# common_board_smd.net
KiCad netlist of a schematic drawn in EAGLE
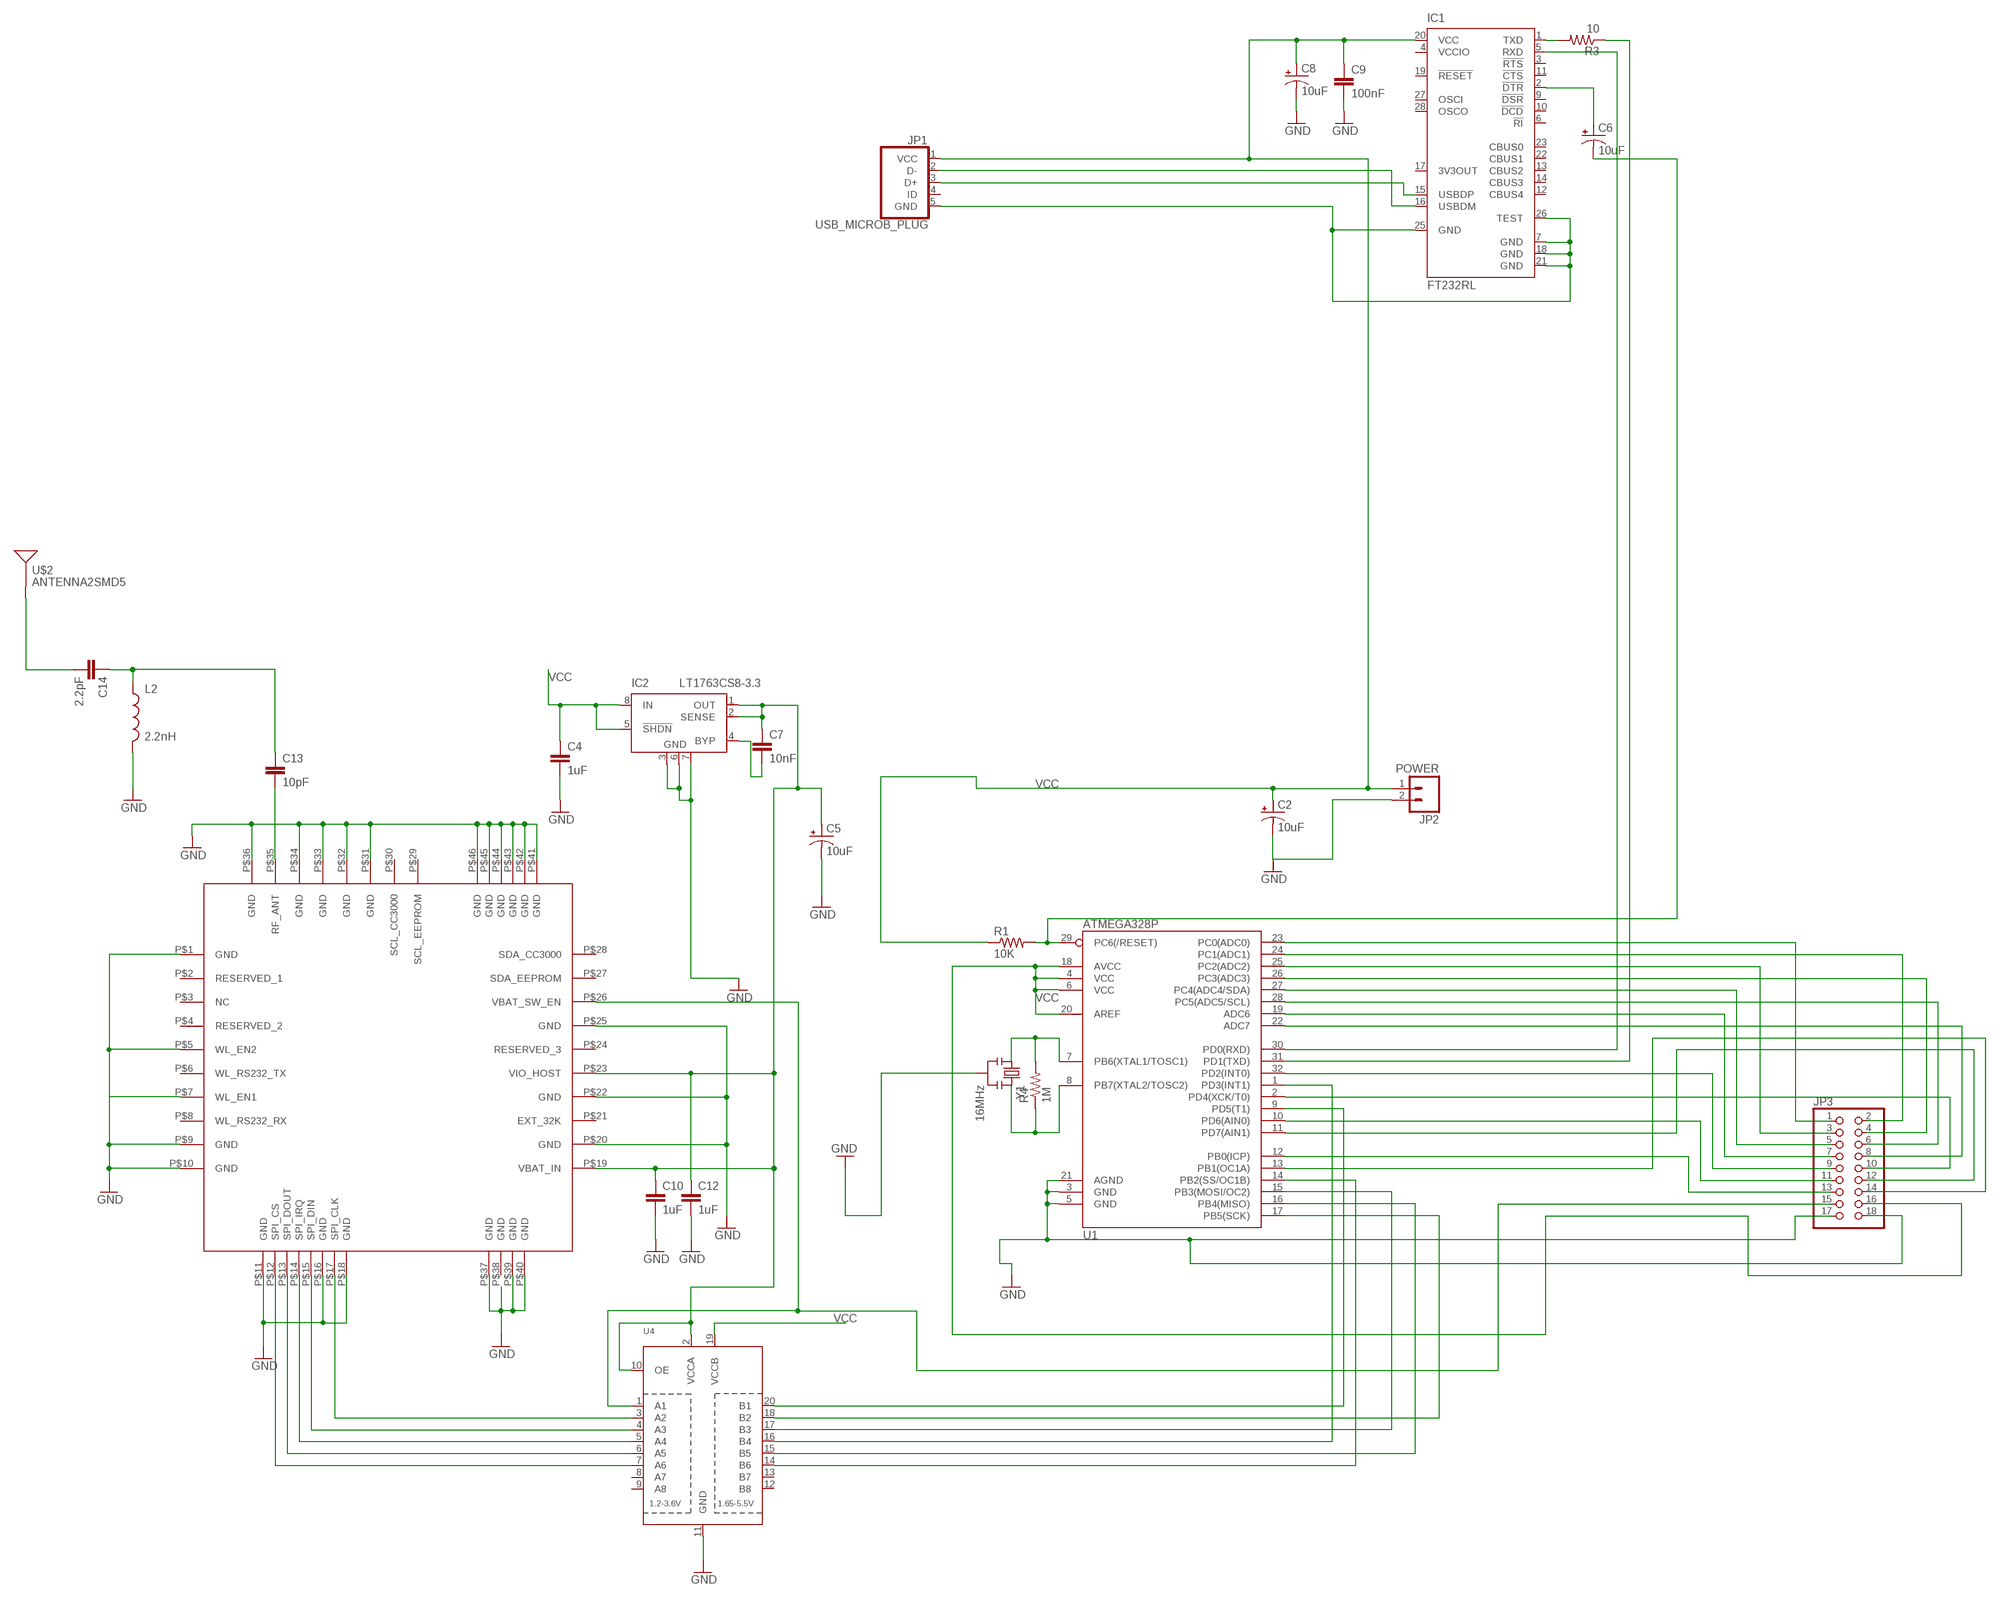
[diagram p0: schematic, sheet 1]

(export (version "E")
  (design (tool "Eeschema 10.0.6"))
  (components
    (comp (ref "C2")
      (value "10uF")
      (footprint "eagle-import:EIA3216")
      (libsource (lib "eagle-import") (part "CAP_POL1206"))
    )
    (comp (ref "C4")
      (value "1uF")
      (footprint "eagle-import:0805")
      (libsource (lib "eagle-import") (part "CAP0805"))
    )
    (comp (ref "C5")
      (value "10uF")
      (footprint "eagle-import:EIA3528")
      (libsource (lib "eagle-import") (part "CAP_POL3528"))
    )
    (comp (ref "C6")
      (value "10uF")
      (footprint "eagle-import:EIA3216")
      (libsource (lib "eagle-import") (part "CAP_POL1206"))
    )
    (comp (ref "C7")
      (value "10nF")
      (footprint "eagle-import:0805")
      (libsource (lib "eagle-import") (part "CAP0805"))
    )
    (comp (ref "C8")
      (value "10uF")
      (footprint "eagle-import:EIA3216")
      (libsource (lib "eagle-import") (part "CAP_POL1206"))
    )
    (comp (ref "C9")
      (value "100nF")
      (footprint "eagle-import:0805")
      (libsource (lib "eagle-import") (part "CAP0805"))
    )
    (comp (ref "C10")
      (value "1uF")
      (footprint "eagle-import:1206")
      (libsource (lib "eagle-import") (part "CAP1206"))
    )
    (comp (ref "C12")
      (value "1uF")
      (footprint "eagle-import:1206")
      (libsource (lib "eagle-import") (part "CAP1206"))
    )
    (comp (ref "C13")
      (value "10pF")
      (footprint "eagle-import:0805")
      (libsource (lib "eagle-import") (part "CAP0805"))
    )
    (comp (ref "C14")
      (value "2.2pF")
      (footprint "eagle-import:0805")
      (libsource (lib "eagle-import") (part "CAP0805"))
    )
    (comp (ref "IC1")
      (value "FT232RL")
      (footprint "eagle-import:SSOP28")
      (libsource (lib "eagle-import") (part "FT232RL"))
    )
    (comp (ref "IC2")
      (value "LT1763CS8-3.3")
      (footprint "eagle-import:SOIC8")
      (libsource (lib "eagle-import") (part "LT1763CS8-3.3"))
    )
    (comp (ref "JP1")
      (value "USB_MICROB_PLUG")
      (footprint "eagle-import:MICRO-B-RA-SMT")
      (libsource (lib "eagle-import") (part "USB_MICROB_PLUG"))
    )
    (comp (ref "JP2")
      (value "POWER")
      (footprint "eagle-import:1X02")
      (libsource (lib "eagle-import") (part "M02PTH"))
    )
    (comp (ref "JP3")
      (value "PINHD-2X9-BIG")
      (footprint "eagle-import:2X09-BIG")
      (libsource (lib "eagle-import") (part "PINHD-2X9-BIG"))
    )
    (comp (ref "L2")
      (value "2.2nH")
      (footprint "eagle-import:0805")
      (libsource (lib "eagle-import") (part "INDUCTOR0805"))
    )
    (comp (ref "R1")
      (value "10K")
      (footprint "eagle-import:0805")
      (libsource (lib "eagle-import") (part "RESISTOR0805-RES"))
    )
    (comp (ref "R3")
      (value "10")
      (footprint "eagle-import:0805")
      (libsource (lib "eagle-import") (part "RESISTOR0805-RES"))
    )
    (comp (ref "R4")
      (value "1M")
      (footprint "eagle-import:0603-RES")
      (libsource (lib "eagle-import") (part "SparkFun-Resistors_RESISTOR0603-RES"))
    )
    (comp (ref "U$1")
      (value "CC3000")
      (footprint "eagle-import:CC3000")
      (fields (field (name "AUTHOR") "Matt Bigarani"))
      (libsource (lib "eagle-import") (part "CC3000"))
    )
    (comp (ref "U$2")
      (value "ANTENNA2SMD5")
      (footprint "eagle-import:ANTENNA-CHIP5")
      (libsource (lib "eagle-import") (part "ANTENNA2SMD5"))
    )
    (comp (ref "U1")
      (value "ATMEGA328P")
      (footprint "eagle-import:TQFP32-08")
      (libsource (lib "eagle-import") (part "ATMEGA328_SMT"))
    )
    (comp (ref "U4")
      (value "TXB0108PWR")
      (footprint "eagle-import:TSSOP20")
      (libsource (lib "eagle-import") (part "TXB0108PWR"))
    )
    (comp (ref "Y1")
      (value "16MHz")
      (footprint "eagle-import:RESONATOR-SMD")
      (libsource (lib "eagle-import") (part "RESONATOR16MHZ"))
    )
  )
  (nets
    (net (code "1") (name "/SCL_CC3000") (class "Default")
      (node (ref "U$1") (pin "P$30") (pinfunction "SCL_CC3000_P$30") (pintype "power_in"))
    )
    (net (code "2") (name "/SCL_EEPROM") (class "Default")
      (node (ref "U$1") (pin "P$29") (pinfunction "SCL_EEPROM_P$29") (pintype "power_in"))
    )
    (net (code "3") (name "/VCC") (class "Default")
      (node (ref "C2") (pin "A") (pinfunction "+_A") (pintype "passive"))
      (node (ref "C4") (pin "1") (pinfunction "1_1") (pintype "passive"))
      (node (ref "C8") (pin "A") (pinfunction "+_A") (pintype "passive"))
      (node (ref "C9") (pin "1") (pinfunction "1_1") (pintype "passive"))
      (node (ref "IC1") (pin "20") (pinfunction "VCC_20") (pintype "power_in"))
      (node (ref "IC2") (pin "5") (pinfunction "~{SHDN}_5") (pintype "input"))
      (node (ref "IC2") (pin "8") (pinfunction "IN_8") (pintype "input"))
      (node (ref "JP1") (pin "1") (pinfunction "VCC_1") (pintype "bidirectional"))
      (node (ref "JP2") (pin "1") (pinfunction "1_1") (pintype "passive"))
      (node (ref "JP3") (pin "16") (pinfunction "16_16") (pintype "passive"))
      (node (ref "R1") (pin "1") (pinfunction "1_1") (pintype "passive"))
      (node (ref "U1") (pin "18") (pinfunction "AVCC_18") (pintype "bidirectional"))
      (node (ref "U1") (pin "20") (pinfunction "AREF_20") (pintype "bidirectional"))
      (node (ref "U1") (pin "4") (pinfunction "VCC_4") (pintype "bidirectional"))
      (node (ref "U1") (pin "6") (pinfunction "VCC_6") (pintype "bidirectional"))
      (node (ref "U4") (pin "19") (pinfunction "VCCB_19") (pintype "bidirectional"))
    )
    (net (code "4") (name "/VCCIO") (class "Default")
      (node (ref "IC1") (pin "4") (pinfunction "VCCIO_4") (pintype "power_in"))
    )
    (net (code "5") (name "GND") (class "Default")
      (node (ref "C10") (pin "2") (pinfunction "2_2") (pintype "passive"))
      (node (ref "C12") (pin "2") (pinfunction "2_2") (pintype "passive"))
      (node (ref "C2") (pin "C") (pinfunction "-_C") (pintype "passive"))
      (node (ref "C4") (pin "2") (pinfunction "2_2") (pintype "passive"))
      (node (ref "C5") (pin "C") (pinfunction "-_C") (pintype "passive"))
      (node (ref "C8") (pin "C") (pinfunction "-_C") (pintype "passive"))
      (node (ref "C9") (pin "2") (pinfunction "2_2") (pintype "passive"))
      (node (ref "IC2") (pin "3") (pinfunction "GND_3") (pintype "power_in"))
      (node (ref "IC2") (pin "6") (pinfunction "GND_6") (pintype "power_in"))
      (node (ref "IC2") (pin "7") (pinfunction "GND_7") (pintype "power_in"))
      (node (ref "JP2") (pin "2") (pinfunction "2_2") (pintype "passive"))
      (node (ref "JP3") (pin "17") (pinfunction "17_17") (pintype "passive"))
      (node (ref "JP3") (pin "18") (pinfunction "18_18") (pintype "passive"))
      (node (ref "L2") (pin "2") (pinfunction "2_2") (pintype "passive"))
      (node (ref "U$1") (pin "P$1") (pinfunction "GND_P$1") (pintype "power_in"))
      (node (ref "U$1") (pin "P$10") (pinfunction "GND_P$10") (pintype "power_in"))
      (node (ref "U$1") (pin "P$11") (pinfunction "GND_P$11") (pintype "power_in"))
      (node (ref "U$1") (pin "P$16") (pinfunction "GND_P$16") (pintype "power_in"))
      (node (ref "U$1") (pin "P$18") (pinfunction "GND_P$18") (pintype "power_in"))
      (node (ref "U$1") (pin "P$20") (pinfunction "GND_P$20") (pintype "bidirectional"))
      (node (ref "U$1") (pin "P$22") (pinfunction "GND_P$22") (pintype "bidirectional"))
      (node (ref "U$1") (pin "P$25") (pinfunction "GND_P$25") (pintype "bidirectional"))
      (node (ref "U$1") (pin "P$31") (pinfunction "GND_P$31") (pintype "power_in"))
      (node (ref "U$1") (pin "P$32") (pinfunction "GND_P$32") (pintype "power_in"))
      (node (ref "U$1") (pin "P$33") (pinfunction "GND_P$33") (pintype "power_in"))
      (node (ref "U$1") (pin "P$34") (pinfunction "GND_P$34") (pintype "power_in"))
      (node (ref "U$1") (pin "P$36") (pinfunction "GND_P$36") (pintype "passive"))
      (node (ref "U$1") (pin "P$37") (pinfunction "GND_P$37") (pintype "power_in"))
      (node (ref "U$1") (pin "P$39") (pinfunction "GND_P$39") (pintype "power_in"))
      (node (ref "U$1") (pin "P$40") (pinfunction "GND_P$40") (pintype "power_in"))
      (node (ref "U$1") (pin "P$41") (pinfunction "GND_P$41") (pintype "power_in"))
      (node (ref "U$1") (pin "P$42") (pinfunction "GND_P$42") (pintype "power_in"))
      (node (ref "U$1") (pin "P$43") (pinfunction "GND_P$43") (pintype "power_in"))
      (node (ref "U$1") (pin "P$44") (pinfunction "GND_P$44") (pintype "power_in"))
      (node (ref "U$1") (pin "P$45") (pinfunction "GND_P$45") (pintype "power_in"))
      (node (ref "U$1") (pin "P$46") (pinfunction "GND_P$46") (pintype "power_in"))
      (node (ref "U$1") (pin "P$5") (pinfunction "WL_EN2_P$5") (pintype "bidirectional"))
      (node (ref "U$1") (pin "P$7") (pinfunction "WL_EN1_P$7") (pintype "bidirectional"))
      (node (ref "U$1") (pin "P$9") (pinfunction "GND_P$9") (pintype "bidirectional"))
      (node (ref "U1") (pin "21") (pinfunction "AGND_21") (pintype "bidirectional"))
      (node (ref "U1") (pin "3") (pinfunction "GND_3") (pintype "bidirectional"))
      (node (ref "U1") (pin "5") (pinfunction "GND_5") (pintype "bidirectional"))
      (node (ref "U4") (pin "11") (pinfunction "GND_11") (pintype "bidirectional"))
      (node (ref "Y1") (pin "2") (pinfunction "2_2") (pintype "passive"))
    )
    (net (code "6") (name "Net-(C5-+)") (class "Default")
      (node (ref "C10") (pin "1") (pinfunction "1_1") (pintype "passive"))
      (node (ref "C12") (pin "1") (pinfunction "1_1") (pintype "passive"))
      (node (ref "C5") (pin "A") (pinfunction "+_A") (pintype "passive"))
      (node (ref "C7") (pin "1") (pinfunction "1_1") (pintype "passive"))
      (node (ref "IC2") (pin "1") (pinfunction "OUT_1") (pintype "passive"))
      (node (ref "IC2") (pin "2") (pinfunction "SENSE_2") (pintype "input"))
      (node (ref "U$1") (pin "P$19") (pinfunction "VBAT_IN_P$19") (pintype "bidirectional"))
      (node (ref "U$1") (pin "P$23") (pinfunction "VIO_HOST_P$23") (pintype "bidirectional"))
      (node (ref "U4") (pin "10") (pinfunction "OE_10") (pintype "bidirectional"))
      (node (ref "U4") (pin "2") (pinfunction "VCCA_2") (pintype "bidirectional"))
    )
    (net (code "7") (name "Net-(C6-+)") (class "Default")
      (node (ref "C6") (pin "A") (pinfunction "+_A") (pintype "passive"))
      (node (ref "IC1") (pin "2") (pinfunction "~{DTR}_2") (pintype "output"))
    )
    (net (code "8") (name "Net-(C6--)") (class "Default")
      (node (ref "C6") (pin "C") (pinfunction "-_C") (pintype "passive"))
      (node (ref "R1") (pin "2") (pinfunction "2_2") (pintype "passive"))
      (node (ref "U1") (pin "29") (pinfunction "PC6(/RESET)_29") (pintype "bidirectional"))
    )
    (net (code "9") (name "Net-(C13-Pad1)") (class "Default")
      (node (ref "C13") (pin "1") (pinfunction "1_1") (pintype "passive"))
      (node (ref "C14") (pin "1") (pinfunction "1_1") (pintype "passive"))
      (node (ref "L2") (pin "1") (pinfunction "1_1") (pintype "passive"))
    )
    (net (code "10") (name "Net-(IC1-RXD)") (class "Default")
      (node (ref "IC1") (pin "5") (pinfunction "RXD_5") (pintype "input"))
      (node (ref "U1") (pin "30") (pinfunction "PD0(RXD)_30") (pintype "bidirectional"))
    )
    (net (code "11") (name "Net-(IC1-TEST)") (class "Default")
      (node (ref "IC1") (pin "18") (pinfunction "GND_18") (pintype "power_in"))
      (node (ref "IC1") (pin "21") (pinfunction "GND_21") (pintype "power_in"))
      (node (ref "IC1") (pin "25") (pinfunction "GND_25") (pintype "power_in"))
      (node (ref "IC1") (pin "26") (pinfunction "TEST_26") (pintype "input"))
      (node (ref "IC1") (pin "7") (pinfunction "GND_7") (pintype "power_in"))
      (node (ref "JP1") (pin "5") (pinfunction "GND_5") (pintype "bidirectional"))
    )
    (net (code "12") (name "Net-(IC1-TXD)") (class "Default")
      (node (ref "IC1") (pin "1") (pinfunction "TXD_1") (pintype "output"))
      (node (ref "R3") (pin "2") (pinfunction "2_2") (pintype "passive"))
    )
    (net (code "13") (name "Net-(IC1-USBDM)") (class "Default")
      (node (ref "IC1") (pin "16") (pinfunction "USBDM_16") (pintype "bidirectional"))
      (node (ref "JP1") (pin "2") (pinfunction "D-_2") (pintype "bidirectional"))
    )
    (net (code "14") (name "Net-(IC1-USBDP)") (class "Default")
      (node (ref "IC1") (pin "15") (pinfunction "USBDP_15") (pintype "bidirectional"))
      (node (ref "JP1") (pin "3") (pinfunction "D+_3") (pintype "bidirectional"))
    )
    (net (code "15") (name "Net-(IC2-BYP)") (class "Default")
      (node (ref "C7") (pin "2") (pinfunction "2_2") (pintype "passive"))
      (node (ref "IC2") (pin "4") (pinfunction "BYP_4") (pintype "input"))
    )
    (net (code "16") (name "Net-(U$1-RF_ANT)") (class "Default")
      (node (ref "C13") (pin "2") (pinfunction "2_2") (pintype "passive"))
      (node (ref "U$1") (pin "P$35") (pinfunction "RF_ANT_P$35") (pintype "bidirectional"))
    )
    (net (code "17") (name "Net-(U$1-SPI_CLK)") (class "Default")
      (node (ref "U$1") (pin "P$17") (pinfunction "SPI_CLK_P$17") (pintype "bidirectional"))
      (node (ref "U4") (pin "3") (pinfunction "A2_3") (pintype "bidirectional"))
    )
    (net (code "18") (name "Net-(U$1-SPI_CS)") (class "Default")
      (node (ref "U$1") (pin "P$12") (pinfunction "SPI_CS_P$12") (pintype "bidirectional"))
      (node (ref "U4") (pin "7") (pinfunction "A6_7") (pintype "bidirectional"))
    )
    (net (code "19") (name "Net-(U$1-SPI_DIN)") (class "Default")
      (node (ref "U$1") (pin "P$15") (pinfunction "SPI_DIN_P$15") (pintype "bidirectional"))
      (node (ref "U4") (pin "4") (pinfunction "A3_4") (pintype "bidirectional"))
    )
    (net (code "20") (name "Net-(U$1-SPI_DOUT)") (class "Default")
      (node (ref "U$1") (pin "P$13") (pinfunction "SPI_DOUT_P$13") (pintype "bidirectional"))
      (node (ref "U4") (pin "6") (pinfunction "A5_6") (pintype "bidirectional"))
    )
    (net (code "21") (name "Net-(U$1-SPI_IRQ)") (class "Default")
      (node (ref "U$1") (pin "P$14") (pinfunction "SPI_IRQ_P$14") (pintype "bidirectional"))
      (node (ref "U4") (pin "5") (pinfunction "A4_5") (pintype "bidirectional"))
    )
    (net (code "22") (name "Net-(U$1-VBAT_SW_EN)") (class "Default")
      (node (ref "JP3") (pin "15") (pinfunction "15_15") (pintype "passive"))
      (node (ref "U$1") (pin "P$26") (pinfunction "VBAT_SW_EN_P$26") (pintype "bidirectional"))
      (node (ref "U4") (pin "1") (pinfunction "A1_1") (pintype "bidirectional"))
    )
    (net (code "23") (name "Net-(U$2-SIGNAL)") (class "Default")
      (node (ref "C14") (pin "2") (pinfunction "2_2") (pintype "passive"))
      (node (ref "U$2") (pin "FEED") (pinfunction "SIGNAL_FEED") (pintype "bidirectional"))
    )
    (net (code "24") (name "Net-(U1-ADC6)") (class "Default")
      (node (ref "JP3") (pin "7") (pinfunction "7_7") (pintype "passive"))
      (node (ref "U1") (pin "19") (pinfunction "ADC6_19") (pintype "bidirectional"))
    )
    (net (code "25") (name "Net-(U1-ADC7)") (class "Default")
      (node (ref "JP3") (pin "8") (pinfunction "8_8") (pintype "passive"))
      (node (ref "U1") (pin "22") (pinfunction "ADC7_22") (pintype "bidirectional"))
    )
    (net (code "26") (name "Net-(U1-PB0(ICP))") (class "Default")
      (node (ref "JP3") (pin "13") (pinfunction "13_13") (pintype "passive"))
      (node (ref "U1") (pin "12") (pinfunction "PB0(ICP)_12") (pintype "bidirectional"))
    )
    (net (code "27") (name "Net-(U1-PB1(OC1A))") (class "Default")
      (node (ref "JP3") (pin "14") (pinfunction "14_14") (pintype "passive"))
      (node (ref "U1") (pin "13") (pinfunction "PB1(OC1A)_13") (pintype "bidirectional"))
    )
    (net (code "28") (name "Net-(U1-PB2(SS{slash}OC1B))") (class "Default")
      (node (ref "U1") (pin "14") (pinfunction "PB2(SS/OC1B)_14") (pintype "bidirectional"))
      (node (ref "U4") (pin "14") (pinfunction "B6_14") (pintype "bidirectional"))
    )
    (net (code "29") (name "Net-(U1-PB3(MOSI{slash}OC2))") (class "Default")
      (node (ref "U1") (pin "15") (pinfunction "PB3(MOSI/OC2)_15") (pintype "bidirectional"))
      (node (ref "U4") (pin "17") (pinfunction "B3_17") (pintype "bidirectional"))
    )
    (net (code "30") (name "Net-(U1-PB4(MISO))") (class "Default")
      (node (ref "U1") (pin "16") (pinfunction "PB4(MISO)_16") (pintype "bidirectional"))
      (node (ref "U4") (pin "15") (pinfunction "B5_15") (pintype "bidirectional"))
    )
    (net (code "31") (name "Net-(U1-PB5(SCK))") (class "Default")
      (node (ref "U1") (pin "17") (pinfunction "PB5(SCK)_17") (pintype "bidirectional"))
      (node (ref "U4") (pin "18") (pinfunction "B2_18") (pintype "bidirectional"))
    )
    (net (code "32") (name "Net-(U1-PB6(XTAL1{slash}TOSC1))") (class "Default")
      (node (ref "R4") (pin "2") (pinfunction "2_2") (pintype "passive"))
      (node (ref "U1") (pin "7") (pinfunction "PB6(XTAL1/TOSC1)_7") (pintype "bidirectional"))
      (node (ref "Y1") (pin "1") (pinfunction "1_1") (pintype "passive"))
    )
    (net (code "33") (name "Net-(U1-PB7(XTAL2{slash}TOSC2))") (class "Default")
      (node (ref "R4") (pin "1") (pinfunction "1_1") (pintype "passive"))
      (node (ref "U1") (pin "8") (pinfunction "PB7(XTAL2/TOSC2)_8") (pintype "bidirectional"))
      (node (ref "Y1") (pin "3") (pinfunction "3_3") (pintype "passive"))
    )
    (net (code "34") (name "Net-(U1-PC0(ADC0))") (class "Default")
      (node (ref "JP3") (pin "1") (pinfunction "1_1") (pintype "passive"))
      (node (ref "U1") (pin "23") (pinfunction "PC0(ADC0)_23") (pintype "bidirectional"))
    )
    (net (code "35") (name "Net-(U1-PC1(ADC1))") (class "Default")
      (node (ref "JP3") (pin "2") (pinfunction "2_2") (pintype "passive"))
      (node (ref "U1") (pin "24") (pinfunction "PC1(ADC1)_24") (pintype "bidirectional"))
    )
    (net (code "36") (name "Net-(U1-PC2(ADC2))") (class "Default")
      (node (ref "JP3") (pin "3") (pinfunction "3_3") (pintype "passive"))
      (node (ref "U1") (pin "25") (pinfunction "PC2(ADC2)_25") (pintype "bidirectional"))
    )
    (net (code "37") (name "Net-(U1-PC3(ADC3))") (class "Default")
      (node (ref "JP3") (pin "4") (pinfunction "4_4") (pintype "passive"))
      (node (ref "U1") (pin "26") (pinfunction "PC3(ADC3)_26") (pintype "bidirectional"))
    )
    (net (code "38") (name "Net-(U1-PC4(ADC4{slash}SDA))") (class "Default")
      (node (ref "JP3") (pin "5") (pinfunction "5_5") (pintype "passive"))
      (node (ref "U1") (pin "27") (pinfunction "PC4(ADC4/SDA)_27") (pintype "bidirectional"))
    )
    (net (code "39") (name "Net-(U1-PC5(ADC5{slash}SCL))") (class "Default")
      (node (ref "JP3") (pin "6") (pinfunction "6_6") (pintype "passive"))
      (node (ref "U1") (pin "28") (pinfunction "PC5(ADC5/SCL)_28") (pintype "bidirectional"))
    )
    (net (code "40") (name "Net-(U1-PD1(TXD))") (class "Default")
      (node (ref "R3") (pin "1") (pinfunction "1_1") (pintype "passive"))
      (node (ref "U1") (pin "31") (pinfunction "PD1(TXD)_31") (pintype "bidirectional"))
    )
    (net (code "41") (name "Net-(U1-PD2(INT0))") (class "Default")
      (node (ref "JP3") (pin "9") (pinfunction "9_9") (pintype "passive"))
      (node (ref "U1") (pin "32") (pinfunction "PD2(INT0)_32") (pintype "bidirectional"))
    )
    (net (code "42") (name "Net-(U1-PD3(INT1))") (class "Default")
      (node (ref "U1") (pin "1") (pinfunction "PD3(INT1)_1") (pintype "bidirectional"))
      (node (ref "U4") (pin "16") (pinfunction "B4_16") (pintype "bidirectional"))
    )
    (net (code "43") (name "Net-(U1-PD4(XCK{slash}T0))") (class "Default")
      (node (ref "JP3") (pin "10") (pinfunction "10_10") (pintype "passive"))
      (node (ref "U1") (pin "2") (pinfunction "PD4(XCK/T0)_2") (pintype "bidirectional"))
    )
    (net (code "44") (name "Net-(U1-PD5(T1))") (class "Default")
      (node (ref "U1") (pin "9") (pinfunction "PD5(T1)_9") (pintype "bidirectional"))
      (node (ref "U4") (pin "20") (pinfunction "B1_20") (pintype "bidirectional"))
    )
    (net (code "45") (name "Net-(U1-PD6(AIN0))") (class "Default")
      (node (ref "JP3") (pin "11") (pinfunction "11_11") (pintype "passive"))
      (node (ref "U1") (pin "10") (pinfunction "PD6(AIN0)_10") (pintype "bidirectional"))
    )
    (net (code "46") (name "Net-(U1-PD7(AIN1))") (class "Default")
      (node (ref "JP3") (pin "12") (pinfunction "12_12") (pintype "passive"))
      (node (ref "U1") (pin "11") (pinfunction "PD7(AIN1)_11") (pintype "bidirectional"))
    )
    (net (code "47") (name "unconnected-(IC1-3V3OUT-Pad17)") (class "Default")
      (node (ref "IC1") (pin "17") (pinfunction "3V3OUT_17") (pintype "output"))
    )
    (net (code "48") (name "unconnected-(IC1-CBUS0-Pad23)") (class "Default")
      (node (ref "IC1") (pin "23") (pinfunction "CBUS0_23") (pintype "bidirectional"))
    )
    (net (code "49") (name "unconnected-(IC1-CBUS1-Pad22)") (class "Default")
      (node (ref "IC1") (pin "22") (pinfunction "CBUS1_22") (pintype "bidirectional"))
    )
    (net (code "50") (name "unconnected-(IC1-CBUS2-Pad13)") (class "Default")
      (node (ref "IC1") (pin "13") (pinfunction "CBUS2_13") (pintype "bidirectional"))
    )
    (net (code "51") (name "unconnected-(IC1-CBUS3-Pad14)") (class "Default")
      (node (ref "IC1") (pin "14") (pinfunction "CBUS3_14") (pintype "bidirectional"))
    )
    (net (code "52") (name "unconnected-(IC1-CBUS4-Pad12)") (class "Default")
      (node (ref "IC1") (pin "12") (pinfunction "CBUS4_12") (pintype "bidirectional"))
    )
    (net (code "53") (name "unconnected-(IC1-OSCI-Pad27)") (class "Default")
      (node (ref "IC1") (pin "27") (pinfunction "OSCI_27") (pintype "input"))
    )
    (net (code "54") (name "unconnected-(IC1-OSCO-Pad28)") (class "Default")
      (node (ref "IC1") (pin "28") (pinfunction "OSCO_28") (pintype "output"))
    )
    (net (code "55") (name "unconnected-(IC1-~{CTS}-Pad11)") (class "Default")
      (node (ref "IC1") (pin "11") (pinfunction "~{CTS}_11") (pintype "input"))
    )
    (net (code "56") (name "unconnected-(IC1-~{DCD}-Pad10)") (class "Default")
      (node (ref "IC1") (pin "10") (pinfunction "~{DCD}_10") (pintype "input"))
    )
    (net (code "57") (name "unconnected-(IC1-~{DSR}-Pad9)") (class "Default")
      (node (ref "IC1") (pin "9") (pinfunction "~{DSR}_9") (pintype "input"))
    )
    (net (code "58") (name "unconnected-(IC1-~{RESET}-Pad19)") (class "Default")
      (node (ref "IC1") (pin "19") (pinfunction "~{RESET}_19") (pintype "input"))
    )
    (net (code "59") (name "unconnected-(IC1-~{RI}-Pad6)") (class "Default")
      (node (ref "IC1") (pin "6") (pinfunction "~{RI}_6") (pintype "input"))
    )
    (net (code "60") (name "unconnected-(IC1-~{RTS}-Pad3)") (class "Default")
      (node (ref "IC1") (pin "3") (pinfunction "~{RTS}_3") (pintype "output"))
    )
    (net (code "61") (name "unconnected-(JP1-ID-Pad4)") (class "Default")
      (node (ref "JP1") (pin "4") (pinfunction "ID_4") (pintype "bidirectional"))
    )
    (net (code "62") (name "unconnected-(U$1-EXT_32K-PadP$21)") (class "Default")
      (node (ref "U$1") (pin "P$21") (pinfunction "EXT_32K_P$21") (pintype "bidirectional"))
    )
    (net (code "63") (name "unconnected-(U$1-GND-PadP$38)") (class "Default")
      (node (ref "U$1") (pin "P$38") (pinfunction "GND_P$38") (pintype "passive"))
    )
    (net (code "64") (name "unconnected-(U$1-NC-PadP$3)") (class "Default")
      (node (ref "U$1") (pin "P$3") (pinfunction "NC_P$3") (pintype "no_connect"))
    )
    (net (code "65") (name "unconnected-(U$1-RESERVED_1-PadP$2)") (class "Default")
      (node (ref "U$1") (pin "P$2") (pinfunction "RESERVED_1_P$2") (pintype "bidirectional"))
    )
    (net (code "66") (name "unconnected-(U$1-RESERVED_2-PadP$4)") (class "Default")
      (node (ref "U$1") (pin "P$4") (pinfunction "RESERVED_2_P$4") (pintype "bidirectional"))
    )
    (net (code "67") (name "unconnected-(U$1-RESERVED_3-PadP$24)") (class "Default")
      (node (ref "U$1") (pin "P$24") (pinfunction "RESERVED_3_P$24") (pintype "bidirectional"))
    )
    (net (code "68") (name "unconnected-(U$1-SDA_CC3000-PadP$28)") (class "Default")
      (node (ref "U$1") (pin "P$28") (pinfunction "SDA_CC3000_P$28") (pintype "bidirectional"))
    )
    (net (code "69") (name "unconnected-(U$1-SDA_EEPROM-PadP$27)") (class "Default")
      (node (ref "U$1") (pin "P$27") (pinfunction "SDA_EEPROM_P$27") (pintype "bidirectional"))
    )
    (net (code "70") (name "unconnected-(U$1-WL_RS232_RX-PadP$8)") (class "Default")
      (node (ref "U$1") (pin "P$8") (pinfunction "WL_RS232_RX_P$8") (pintype "bidirectional"))
    )
    (net (code "71") (name "unconnected-(U$1-WL_RS232_TX-PadP$6)") (class "Default")
      (node (ref "U$1") (pin "P$6") (pinfunction "WL_RS232_TX_P$6") (pintype "bidirectional"))
    )
    (net (code "72") (name "unconnected-(U4-A7-Pad8)") (class "Default")
      (node (ref "U4") (pin "8") (pinfunction "A7_8") (pintype "bidirectional"))
    )
    (net (code "73") (name "unconnected-(U4-A8-Pad9)") (class "Default")
      (node (ref "U4") (pin "9") (pinfunction "A8_9") (pintype "bidirectional"))
    )
    (net (code "74") (name "unconnected-(U4-B7-Pad13)") (class "Default")
      (node (ref "U4") (pin "13") (pinfunction "B7_13") (pintype "bidirectional"))
    )
    (net (code "75") (name "unconnected-(U4-B8-Pad12)") (class "Default")
      (node (ref "U4") (pin "12") (pinfunction "B8_12") (pintype "bidirectional"))
    )
  )
)
